# headstageNano16CMOS.net
KiCad netlist of a schematic drawn in EAGLE
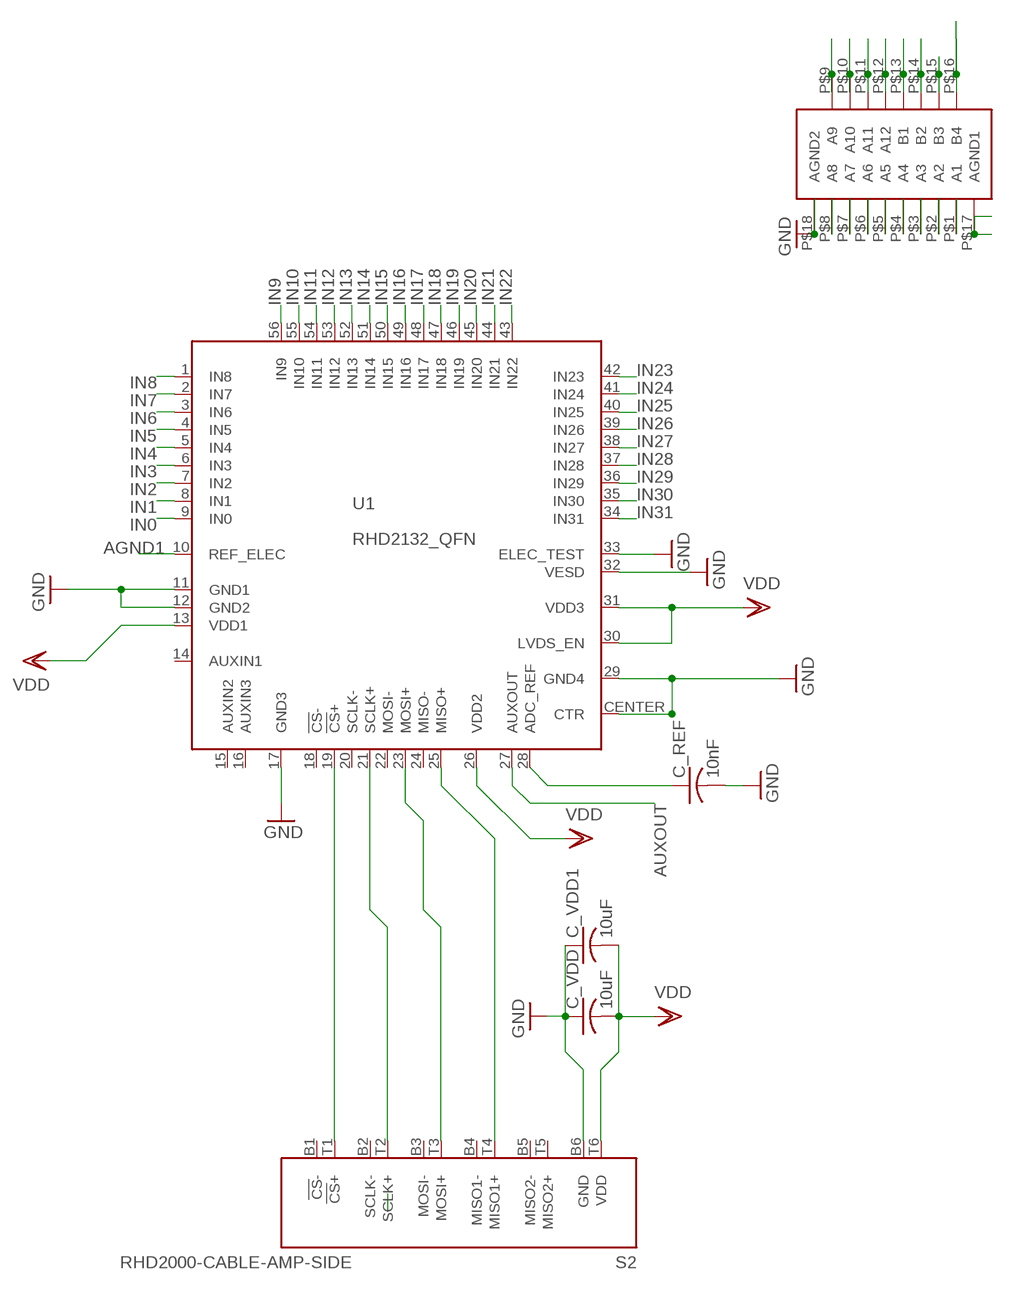
[diagram p0: schematic, sheet 1]

(export (version "E")
  (design (tool "Eeschema 10.0.6"))
  (components
    (comp (ref "C_REF")
      (value "10nF")
      (footprint "eagle-import:C0402K")
      (libsource (lib "eagle-import") (part "C-USC0402K"))
    )
    (comp (ref "C_VDD")
      (value "10uF")
      (footprint "eagle-import:C0402K")
      (libsource (lib "eagle-import") (part "C-USC0402K"))
    )
    (comp (ref "C_VDD1")
      (value "10uF")
      (footprint "eagle-import:C0402K")
      (libsource (lib "eagle-import") (part "C-USC0402K"))
    )
    (comp (ref "S2")
      (value "RHD2000-CABLE-AMP-SIDE")
      (footprint "eagle-import:OMNETICS_PZN-12-AA")
      (libsource (lib "eagle-import") (part "RHD2000-CABLE-AMP-SIDE"))
    )
    (comp (ref "U$1")
      (value "OMNETICS_FE18")
      (footprint "eagle-import:OMNETICS_FE18")
      (libsource (lib "eagle-import") (part "OMNETICS_FE18"))
    )
    (comp (ref "U1")
      (value "RHD2132_QFN")
      (footprint "eagle-import:QFN56_8_X_8_LARGE")
      (libsource (lib "eagle-import") (part "RHD2132_QFN"))
    )
  )
  (nets
    (net (code "1") (name "/AGND1") (class "Default")
      (node (ref "U$1") (pin "P$17") (pinfunction "AGND1_P$17") (pintype "bidirectional"))
      (node (ref "U1") (pin "10") (pinfunction "REF_ELEC_10") (pintype "input"))
    )
    (net (code "2") (name "/AUXOUT") (class "Default")
      (node (ref "U1") (pin "27") (pinfunction "AUXOUT_27") (pintype "tri_state"))
    )
    (net (code "3") (name "/IN0") (class "Default")
      (node (ref "U1") (pin "9") (pinfunction "IN0_9") (pintype "input"))
    )
    (net (code "4") (name "/IN1") (class "Default")
      (node (ref "U1") (pin "8") (pinfunction "IN1_8") (pintype "input"))
    )
    (net (code "5") (name "/IN2") (class "Default")
      (node (ref "U1") (pin "7") (pinfunction "IN2_7") (pintype "input"))
    )
    (net (code "6") (name "/IN3") (class "Default")
      (node (ref "U1") (pin "6") (pinfunction "IN3_6") (pintype "input"))
    )
    (net (code "7") (name "/IN4") (class "Default")
      (node (ref "U1") (pin "5") (pinfunction "IN4_5") (pintype "input"))
    )
    (net (code "8") (name "/IN5") (class "Default")
      (node (ref "U1") (pin "4") (pinfunction "IN5_4") (pintype "input"))
    )
    (net (code "9") (name "/IN6") (class "Default")
      (node (ref "U1") (pin "3") (pinfunction "IN6_3") (pintype "input"))
    )
    (net (code "10") (name "/IN7") (class "Default")
      (node (ref "U1") (pin "2") (pinfunction "IN7_2") (pintype "input"))
    )
    (net (code "11") (name "/IN8") (class "Default")
      (node (ref "U$1") (pin "P$14") (pinfunction "B2_P$14") (pintype "bidirectional"))
      (node (ref "U1") (pin "1") (pinfunction "IN8_1") (pintype "input"))
    )
    (net (code "12") (name "/IN9") (class "Default")
      (node (ref "U$1") (pin "P$16") (pinfunction "B4_P$16") (pintype "bidirectional"))
      (node (ref "U1") (pin "56") (pinfunction "IN9_56") (pintype "input"))
    )
    (net (code "13") (name "/IN10") (class "Default")
      (node (ref "U$1") (pin "P$1") (pinfunction "A1_P$1") (pintype "bidirectional"))
      (node (ref "U1") (pin "55") (pinfunction "IN10_55") (pintype "input"))
    )
    (net (code "14") (name "/IN11") (class "Default")
      (node (ref "U$1") (pin "P$2") (pinfunction "A2_P$2") (pintype "bidirectional"))
      (node (ref "U1") (pin "54") (pinfunction "IN11_54") (pintype "input"))
    )
    (net (code "15") (name "/IN12") (class "Default")
      (node (ref "U$1") (pin "P$15") (pinfunction "B3_P$15") (pintype "bidirectional"))
      (node (ref "U1") (pin "53") (pinfunction "IN12_53") (pintype "input"))
    )
    (net (code "16") (name "/IN13") (class "Default")
      (node (ref "U$1") (pin "P$3") (pinfunction "A3_P$3") (pintype "bidirectional"))
      (node (ref "U1") (pin "52") (pinfunction "IN13_52") (pintype "input"))
    )
    (net (code "17") (name "/IN14") (class "Default")
      (node (ref "U$1") (pin "P$12") (pinfunction "A12_P$12") (pintype "bidirectional"))
      (node (ref "U1") (pin "51") (pinfunction "IN14_51") (pintype "input"))
    )
    (net (code "18") (name "/IN15") (class "Default")
      (node (ref "U$1") (pin "P$13") (pinfunction "B1_P$13") (pintype "bidirectional"))
      (node (ref "U1") (pin "50") (pinfunction "IN15_50") (pintype "input"))
    )
    (net (code "19") (name "/IN16") (class "Default")
      (node (ref "U$1") (pin "P$5") (pinfunction "A5_P$5") (pintype "bidirectional"))
      (node (ref "U1") (pin "49") (pinfunction "IN16_49") (pintype "input"))
    )
    (net (code "20") (name "/IN17") (class "Default")
      (node (ref "U$1") (pin "P$4") (pinfunction "A4_P$4") (pintype "bidirectional"))
      (node (ref "U1") (pin "48") (pinfunction "IN17_48") (pintype "input"))
    )
    (net (code "21") (name "/IN18") (class "Default")
      (node (ref "U$1") (pin "P$6") (pinfunction "A6_P$6") (pintype "bidirectional"))
      (node (ref "U1") (pin "47") (pinfunction "IN18_47") (pintype "input"))
    )
    (net (code "22") (name "/IN19") (class "Default")
      (node (ref "U$1") (pin "P$7") (pinfunction "A7_P$7") (pintype "bidirectional"))
      (node (ref "U1") (pin "46") (pinfunction "IN19_46") (pintype "input"))
    )
    (net (code "23") (name "/IN20") (class "Default")
      (node (ref "U$1") (pin "P$10") (pinfunction "A10_P$10") (pintype "bidirectional"))
      (node (ref "U1") (pin "45") (pinfunction "IN20_45") (pintype "input"))
    )
    (net (code "24") (name "/IN21") (class "Default")
      (node (ref "U$1") (pin "P$8") (pinfunction "A8_P$8") (pintype "bidirectional"))
      (node (ref "U1") (pin "44") (pinfunction "IN21_44") (pintype "input"))
    )
    (net (code "25") (name "/IN22") (class "Default")
      (node (ref "U$1") (pin "P$9") (pinfunction "A9_P$9") (pintype "bidirectional"))
      (node (ref "U1") (pin "43") (pinfunction "IN22_43") (pintype "input"))
    )
    (net (code "26") (name "/IN23") (class "Default")
      (node (ref "U$1") (pin "P$11") (pinfunction "A11_P$11") (pintype "bidirectional"))
      (node (ref "U1") (pin "42") (pinfunction "IN23_42") (pintype "input"))
    )
    (net (code "27") (name "/IN24") (class "Default")
      (node (ref "U1") (pin "41") (pinfunction "IN24_41") (pintype "input"))
    )
    (net (code "28") (name "/IN25") (class "Default")
      (node (ref "U1") (pin "40") (pinfunction "IN25_40") (pintype "input"))
    )
    (net (code "29") (name "/IN26") (class "Default")
      (node (ref "U1") (pin "39") (pinfunction "IN26_39") (pintype "input"))
    )
    (net (code "30") (name "/IN27") (class "Default")
      (node (ref "U1") (pin "38") (pinfunction "IN27_38") (pintype "input"))
    )
    (net (code "31") (name "/IN28") (class "Default")
      (node (ref "U1") (pin "37") (pinfunction "IN28_37") (pintype "input"))
    )
    (net (code "32") (name "/IN29") (class "Default")
      (node (ref "U1") (pin "36") (pinfunction "IN29_36") (pintype "input"))
    )
    (net (code "33") (name "/IN30") (class "Default")
      (node (ref "U1") (pin "35") (pinfunction "IN30_35") (pintype "input"))
    )
    (net (code "34") (name "/IN31") (class "Default")
      (node (ref "U1") (pin "34") (pinfunction "IN31_34") (pintype "input"))
    )
    (net (code "35") (name "GND") (class "Default")
      (node (ref "C_REF") (pin "2") (pinfunction "2_2") (pintype "passive"))
      (node (ref "C_VDD") (pin "1") (pinfunction "1_1") (pintype "passive"))
      (node (ref "C_VDD1") (pin "1") (pinfunction "1_1") (pintype "passive"))
      (node (ref "S2") (pin "B6") (pinfunction "GND_B6") (pintype "power_in"))
      (node (ref "U$1") (pin "P$18") (pinfunction "AGND2_P$18") (pintype "bidirectional"))
      (node (ref "U1") (pin "11") (pinfunction "GND1_11") (pintype "power_in"))
      (node (ref "U1") (pin "12") (pinfunction "GND2_12") (pintype "power_in"))
      (node (ref "U1") (pin "17") (pinfunction "GND3_17") (pintype "power_in"))
      (node (ref "U1") (pin "29") (pinfunction "GND4_29") (pintype "power_in"))
      (node (ref "U1") (pin "32") (pinfunction "VESD_32") (pintype "power_in"))
      (node (ref "U1") (pin "33") (pinfunction "ELEC_TEST_33") (pintype "input"))
      (node (ref "U1") (pin "CENTER") (pinfunction "CTR_CENTER") (pintype "power_in"))
    )
    (net (code "36") (name "Net-(S2-MOSI+)") (class "Default")
      (node (ref "S2") (pin "T3") (pinfunction "MOSI+_T3") (pintype "bidirectional"))
      (node (ref "U1") (pin "23") (pinfunction "MOSI+_23") (pintype "input"))
    )
    (net (code "37") (name "Net-(S2-SCLK+)") (class "Default")
      (node (ref "S2") (pin "T2") (pinfunction "SCLK+_T2") (pintype "bidirectional"))
      (node (ref "U1") (pin "21") (pinfunction "SCLK+_21") (pintype "input"))
    )
    (net (code "38") (name "Net-(S2-~{CS}+)") (class "Default")
      (node (ref "S2") (pin "T1") (pinfunction "~{CS}+_T1") (pintype "bidirectional"))
      (node (ref "U1") (pin "19") (pinfunction "~{CS}+_19") (pintype "input"))
    )
    (net (code "39") (name "Net-(U1-ADC_REF)") (class "Default")
      (node (ref "C_REF") (pin "1") (pinfunction "1_1") (pintype "passive"))
      (node (ref "U1") (pin "28") (pinfunction "ADC_REF_28") (pintype "passive"))
    )
    (net (code "40") (name "VDD") (class "Default")
      (node (ref "C_VDD") (pin "2") (pinfunction "2_2") (pintype "passive"))
      (node (ref "C_VDD1") (pin "2") (pinfunction "2_2") (pintype "passive"))
      (node (ref "S2") (pin "T4") (pinfunction "MISO1+_T4") (pintype "bidirectional"))
      (node (ref "S2") (pin "T6") (pinfunction "VDD_T6") (pintype "bidirectional"))
      (node (ref "U1") (pin "13") (pinfunction "VDD1_13") (pintype "power_in"))
      (node (ref "U1") (pin "25") (pinfunction "MISO+_25") (pintype "output"))
      (node (ref "U1") (pin "26") (pinfunction "VDD2_26") (pintype "power_in"))
      (node (ref "U1") (pin "30") (pinfunction "LVDS_EN_30") (pintype "input"))
      (node (ref "U1") (pin "31") (pinfunction "VDD3_31") (pintype "power_in"))
    )
    (net (code "41") (name "unconnected-(S2-MISO1--PadB4)") (class "Default")
      (node (ref "S2") (pin "B4") (pinfunction "MISO1-_B4") (pintype "bidirectional"))
    )
    (net (code "42") (name "unconnected-(S2-MISO2+-PadT5)") (class "Default")
      (node (ref "S2") (pin "T5") (pinfunction "MISO2+_T5") (pintype "bidirectional"))
    )
    (net (code "43") (name "unconnected-(S2-MISO2--PadB5)") (class "Default")
      (node (ref "S2") (pin "B5") (pinfunction "MISO2-_B5") (pintype "bidirectional"))
    )
    (net (code "44") (name "unconnected-(S2-MOSI--PadB3)") (class "Default")
      (node (ref "S2") (pin "B3") (pinfunction "MOSI-_B3") (pintype "bidirectional"))
    )
    (net (code "45") (name "unconnected-(S2-SCLK--PadB2)") (class "Default")
      (node (ref "S2") (pin "B2") (pinfunction "SCLK-_B2") (pintype "bidirectional"))
    )
    (net (code "46") (name "unconnected-(S2-~{CS}--PadB1)") (class "Default")
      (node (ref "S2") (pin "B1") (pinfunction "~{CS}-_B1") (pintype "bidirectional"))
    )
    (net (code "47") (name "unconnected-(U1-AUXIN1-Pad14)") (class "Default")
      (node (ref "U1") (pin "14") (pinfunction "AUXIN1_14") (pintype "input"))
    )
    (net (code "48") (name "unconnected-(U1-AUXIN2-Pad15)") (class "Default")
      (node (ref "U1") (pin "15") (pinfunction "AUXIN2_15") (pintype "input"))
    )
    (net (code "49") (name "unconnected-(U1-AUXIN3-Pad16)") (class "Default")
      (node (ref "U1") (pin "16") (pinfunction "AUXIN3_16") (pintype "input"))
    )
    (net (code "50") (name "unconnected-(U1-MISO--Pad24)") (class "Default")
      (node (ref "U1") (pin "24") (pinfunction "MISO-_24") (pintype "output"))
    )
    (net (code "51") (name "unconnected-(U1-MOSI--Pad22)") (class "Default")
      (node (ref "U1") (pin "22") (pinfunction "MOSI-_22") (pintype "input"))
    )
    (net (code "52") (name "unconnected-(U1-SCLK--Pad20)") (class "Default")
      (node (ref "U1") (pin "20") (pinfunction "SCLK-_20") (pintype "input"))
    )
    (net (code "53") (name "unconnected-(U1-~{CS}--Pad18)") (class "Default")
      (node (ref "U1") (pin "18") (pinfunction "~{CS}-_18") (pintype "input"))
    )
  )
)
